# BC-MPR_Interface.net
KiCad netlist of a schematic drawn in Altium Designer
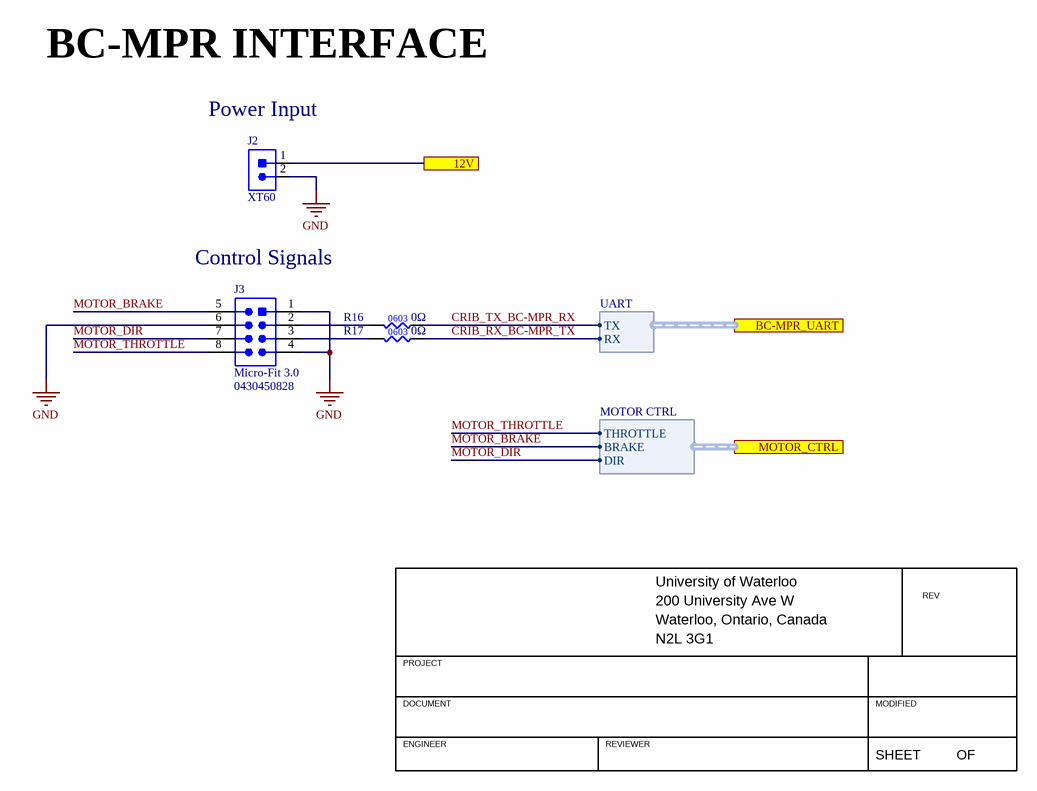
[diagram p0: BC-MPR Interface.SchDoc]

(export (version "E")
  (design (tool "Eeschema 10.0.6"))
  (components
    (comp (ref "J2")
      (value "CON_2POS_XT60")
      (footprint "XT60")
      (description "XT60 CONNECTORS MALE/FEMALE PAIR")
      (fields (field (name "PACKAGE/FOOTPRINT") "XT60"))
      (libsource (lib "Personal_Schematic_Library_2022") (part "CON_2POS_XT60"))
    )
    (comp (ref "J3")
      (value "0430450828")
      (footprint "MOLEX-0430450828")
      (description "CONN HEADER VERT 8POS 3MM")
      (fields
        (field (name "FAMILY") "Micro-Fit 3.0")
        (field (name "MANUFACTURER PART NUMBER 1") "0430450828")
      )
      (libsource (lib "Personal_Schematic_Library_2022") (part "CON_MOLEX-HDR_4x2_TH"))
    )
    (comp (ref "R16")
      (value "0Ω")
      (footprint "RES0603")
      (description "RES 0 OHM JUMPER 1/10W 0603")
      (fields (field (name "Comment") "RES_0Ω_0603"))
      (libsource (lib "Personal_Schematic_Library_2022") (part "RES_0Ω_0603"))
    )
    (comp (ref "R17")
      (value "0Ω")
      (footprint "RES0603")
      (description "RES 0 OHM JUMPER 1/10W 0603")
      (fields (field (name "Comment") "RES_0Ω_0603"))
      (libsource (lib "Personal_Schematic_Library_2022") (part "RES_0Ω_0603"))
    )
  )
  (nets
    (net (code "4") (name "/12V") (class "Default")
      (node (ref "J2") (pin "1") (pinfunction "1_1") (pintype "passive"))
    )
    (net (code "5") (name "/CRIB_RX_BC-MPR_TX") (class "Default")
      (node (ref "R17") (pin "1") (pinfunction "1_1") (pintype "passive"))
    )
    (net (code "6") (name "/CRIB_TX_BC-MPR_RX") (class "Default")
      (node (ref "R16") (pin "1") (pinfunction "1_1") (pintype "passive"))
    )
    (net (code "7") (name "/MOTOR_BRAKE") (class "Default")
      (node (ref "J3") (pin "5") (pinfunction "5_5") (pintype "passive"))
    )
    (net (code "8") (name "/MOTOR_DIR") (class "Default")
      (node (ref "J3") (pin "7") (pinfunction "7_7") (pintype "passive"))
    )
    (net (code "9") (name "/MOTOR_THROTTLE") (class "Default")
      (node (ref "J3") (pin "8") (pinfunction "8_8") (pintype "passive"))
    )
    (net (code "12") (name "GND") (class "Default")
      (node (ref "J2") (pin "2") (pinfunction "2_2") (pintype "passive"))
      (node (ref "J3") (pin "1") (pinfunction "1_1") (pintype "passive"))
      (node (ref "J3") (pin "4") (pinfunction "4_4") (pintype "passive"))
      (node (ref "J3") (pin "6") (pinfunction "6_6") (pintype "passive"))
    )
    (net (code "13") (name "Net-(J3-Pad2)") (class "Default")
      (node (ref "J3") (pin "2") (pinfunction "2_2") (pintype "passive"))
      (node (ref "R16") (pin "2") (pinfunction "2_2") (pintype "passive"))
    )
    (net (code "14") (name "Net-(J3-Pad3)") (class "Default")
      (node (ref "J3") (pin "3") (pinfunction "3_3") (pintype "passive"))
      (node (ref "R17") (pin "2") (pinfunction "2_2") (pintype "passive"))
    )
  )
)
